# 7_RK3399_MIPI-CSI_I2C.net
KiCad netlist of a schematic drawn in Altium Designer
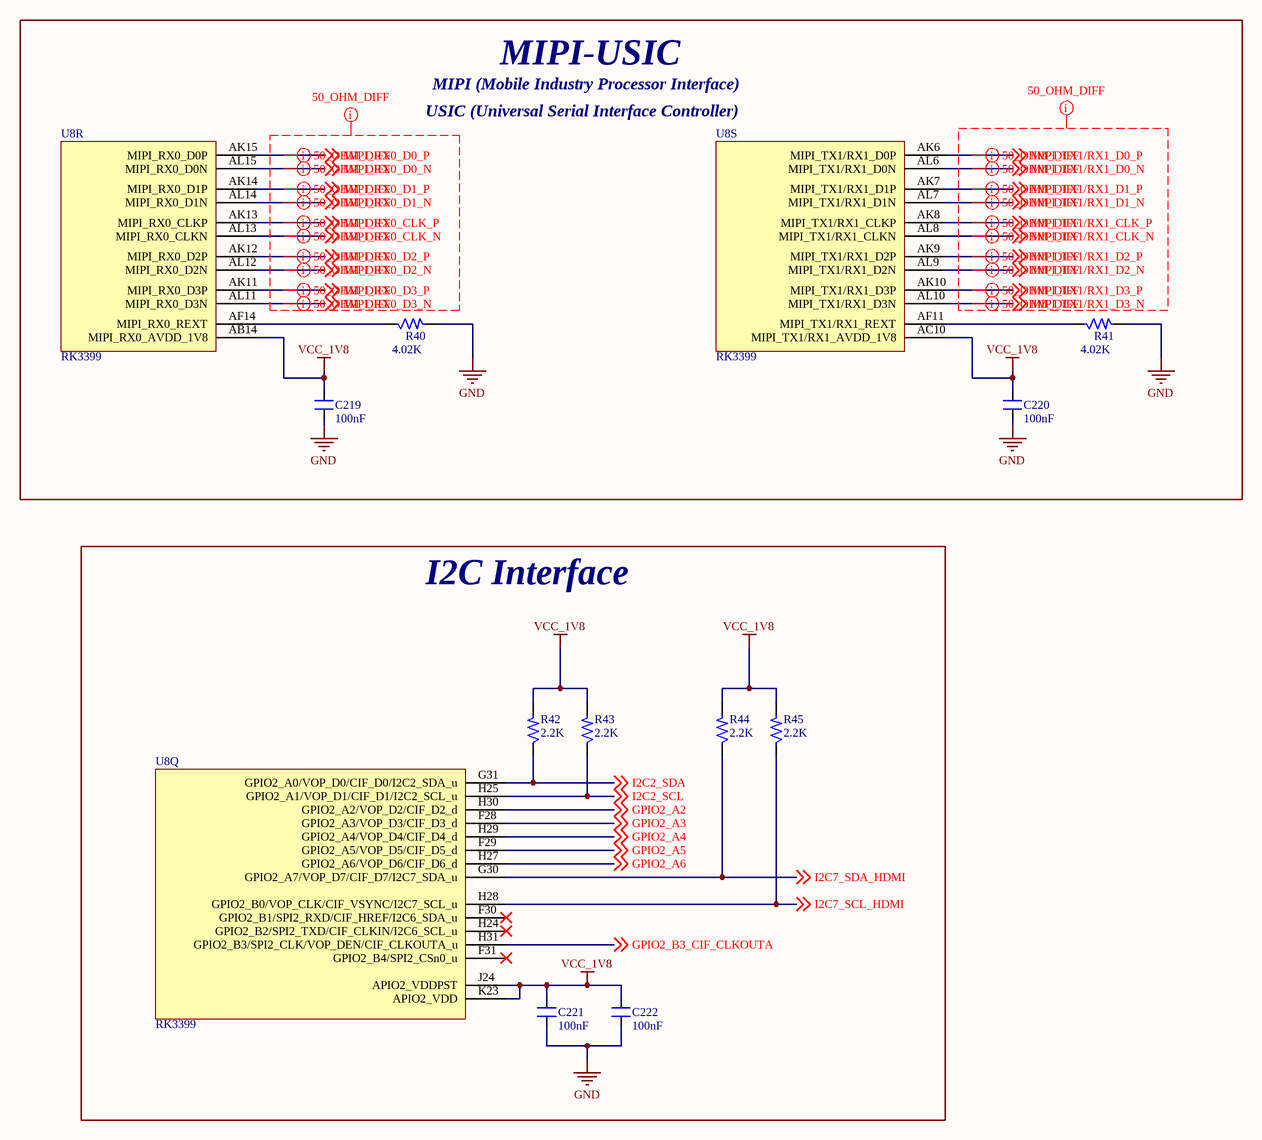
[diagram p0: [7] RK3399_MIPI-CSI_I2C.SchDoc]

(export (version "E")
  (design (tool "Eeschema 10.0.6"))
  (components
    (comp (ref "C219")
      (value "100nF")
      (footprint "CAP_0201")
      (description "0.1µF ±10% 25V Ceramic Capacitor X5R 0201 (0603 Metric)")
      (fields
        (field (name "MANUFACTURER") "TDK Corporation")
        (field (name "MANUFACTURER PART NUMBER") "C0603X5R1E104K030BB")
      )
      (libsource (lib "EsteemPCB_SOM_Course_intlib") (part "CAP_100nF-25V-10%-0201"))
    )
    (comp (ref "C220")
      (value "100nF")
      (footprint "CAP_0201")
      (description "0.1µF ±10% 25V Ceramic Capacitor X5R 0201 (0603 Metric)")
      (fields
        (field (name "MANUFACTURER") "TDK Corporation")
        (field (name "MANUFACTURER PART NUMBER") "C0603X5R1E104K030BB")
      )
      (libsource (lib "EsteemPCB_SOM_Course_intlib") (part "CAP_100nF-25V-10%-0201"))
    )
    (comp (ref "C221")
      (value "100nF")
      (footprint "CAP_0201")
      (description "0.1µF ±10% 25V Ceramic Capacitor X5R 0201 (0603 Metric)")
      (fields
        (field (name "MANUFACTURER") "TDK Corporation")
        (field (name "MANUFACTURER PART NUMBER") "C0603X5R1E104K030BB")
      )
      (libsource (lib "EsteemPCB_SOM_Course_intlib") (part "CAP_100nF-25V-10%-0201"))
    )
    (comp (ref "C222")
      (value "100nF")
      (footprint "CAP_0201")
      (description "0.1µF ±10% 25V Ceramic Capacitor X5R 0201 (0603 Metric)")
      (fields
        (field (name "MANUFACTURER") "TDK Corporation")
        (field (name "MANUFACTURER PART NUMBER") "C0603X5R1E104K030BB")
      )
      (libsource (lib "EsteemPCB_SOM_Course_intlib") (part "CAP_100nF-25V-10%-0201"))
    )
    (comp (ref "R40")
      (value "4.02K")
      (footprint "RES_0201")
      (description "4.02 kOhms ±1% 0.05W, 1/20W Chip Resistor 0201 (0603 Metric) Thick Film")
      (fields
        (field (name "MANUFACTURER") "Yageo")
        (field (name "MANUFACTURER PART NUMBER") "RC0201FR-074K02L")
      )
      (libsource (lib "EsteemPCB_SOM_Course_intlib") (part "RES_4.02K-0.05W-1%-0201"))
    )
    (comp (ref "R41")
      (value "4.02K")
      (footprint "RES_0201")
      (description "4.02 kOhms ±1% 0.05W, 1/20W Chip Resistor 0201 (0603 Metric) Thick Film")
      (fields
        (field (name "MANUFACTURER") "Yageo")
        (field (name "MANUFACTURER PART NUMBER") "RC0201FR-074K02L")
      )
      (libsource (lib "EsteemPCB_SOM_Course_intlib") (part "RES_4.02K-0.05W-1%-0201"))
    )
    (comp (ref "R42")
      (value "2.2K")
      (footprint "RES_0201")
      (description "2.2 kOhms ±1% 0.05W, 1/20W Chip Resistor 0201 (0603 Metric) Thick Film")
      (fields
        (field (name "MANUFACTURER") "Stackpole Electronics Inc")
        (field (name "MANUFACTURER PART NUMBER") "RMCF0201FT2K20")
      )
      (libsource (lib "EsteemPCB_SOM_Course_intlib") (part "RES_2.2K-0.05W-1%-0201"))
    )
    (comp (ref "R43")
      (value "2.2K")
      (footprint "RES_0201")
      (description "2.2 kOhms ±1% 0.05W, 1/20W Chip Resistor 0201 (0603 Metric) Thick Film")
      (fields
        (field (name "MANUFACTURER") "Stackpole Electronics Inc")
        (field (name "MANUFACTURER PART NUMBER") "RMCF0201FT2K20")
      )
      (libsource (lib "EsteemPCB_SOM_Course_intlib") (part "RES_2.2K-0.05W-1%-0201"))
    )
    (comp (ref "R44")
      (value "2.2K")
      (footprint "RES_0201")
      (description "2.2 kOhms ±1% 0.05W, 1/20W Chip Resistor 0201 (0603 Metric) Thick Film")
      (fields
        (field (name "MANUFACTURER") "Stackpole Electronics Inc")
        (field (name "MANUFACTURER PART NUMBER") "RMCF0201FT2K20")
      )
      (libsource (lib "EsteemPCB_SOM_Course_intlib") (part "RES_2.2K-0.05W-1%-0201"))
    )
    (comp (ref "R45")
      (value "2.2K")
      (footprint "RES_0201")
      (description "2.2 kOhms ±1% 0.05W, 1/20W Chip Resistor 0201 (0603 Metric) Thick Film")
      (fields
        (field (name "MANUFACTURER") "Stackpole Electronics Inc")
        (field (name "MANUFACTURER PART NUMBER") "RMCF0201FT2K20")
      )
      (libsource (lib "EsteemPCB_SOM_Course_intlib") (part "RES_2.2K-0.05W-1%-0201"))
    )
    (comp (ref "U8")
      (value "RK3399")
      (footprint "FBGA828_23_826X826")
      (description "RK3399 is a low power, high performance processor for computing, personal mobile.")
      (fields (field (name "MANUFACTURER") "Rockchip"))
      (libsource (lib "EsteemPCB_SOM_Course_intlib") (part "IC_RK3399-FCBGA828"))
    )
  )
  (nets
    (net (code "1") (name "GND") (class "Default")
      (node (ref "C219") (pin "1") (pinfunction "1_1") (pintype "passive"))
      (node (ref "C220") (pin "1") (pinfunction "1_1") (pintype "passive"))
      (node (ref "C221") (pin "1") (pinfunction "1_1") (pintype "passive"))
      (node (ref "C222") (pin "1") (pinfunction "1_1") (pintype "passive"))
      (node (ref "R40") (pin "2") (pinfunction "2_2") (pintype "passive"))
      (node (ref "R41") (pin "2") (pinfunction "2_2") (pintype "passive"))
    )
    (net (code "2") (name "GPIO2_A2") (class "Default")
      (node (ref "U8") (pin "H30") (pinfunction "GPIO2_A2/VOP_D2/CIF_D2_d_H30") (pintype "passive"))
    )
    (net (code "3") (name "GPIO2_A3") (class "Default")
      (node (ref "U8") (pin "F28") (pinfunction "GPIO2_A3/VOP_D3/CIF_D3_d_F28") (pintype "passive"))
    )
    (net (code "4") (name "GPIO2_A4") (class "Default")
      (node (ref "U8") (pin "H29") (pinfunction "GPIO2_A4/VOP_D4/CIF_D4_d_H29") (pintype "passive"))
    )
    (net (code "5") (name "GPIO2_A5") (class "Default")
      (node (ref "U8") (pin "F29") (pinfunction "GPIO2_A5/VOP_D5/CIF_D5_d_F29") (pintype "passive"))
    )
    (net (code "6") (name "GPIO2_A6") (class "Default")
      (node (ref "U8") (pin "H27") (pinfunction "GPIO2_A6/VOP_D6/CIF_D6_d_H27") (pintype "passive"))
    )
    (net (code "7") (name "GPIO2_B3_CIF_CLKOUTA") (class "Default")
      (node (ref "U8") (pin "H31") (pinfunction "GPIO2_B3/SPI2_CLK/VOP_DEN/CIF_CLKOUTA_u_H31") (pintype "passive"))
    )
    (net (code "8") (name "I2C2_SCL") (class "Default")
      (node (ref "R43") (pin "1") (pinfunction "1_1") (pintype "passive"))
      (node (ref "U8") (pin "H25") (pinfunction "GPIO2_A1/VOP_D1/CIF_D1/I2C2_SCL_u_H25") (pintype "passive"))
    )
    (net (code "9") (name "I2C2_SDA") (class "Default")
      (node (ref "R42") (pin "1") (pinfunction "1_1") (pintype "passive"))
      (node (ref "U8") (pin "G31") (pinfunction "GPIO2_A0/VOP_D0/CIF_D0/I2C2_SDA_u_G31") (pintype "passive"))
    )
    (net (code "10") (name "I2C7_SCL_HDMI") (class "Default")
      (node (ref "R45") (pin "1") (pinfunction "1_1") (pintype "passive"))
      (node (ref "U8") (pin "H28") (pinfunction "GPIO2_B0/VOP_CLK/CIF_VSYNC/I2C7_SCL_u_H28") (pintype "passive"))
    )
    (net (code "11") (name "I2C7_SDA_HDMI") (class "Default")
      (node (ref "R44") (pin "1") (pinfunction "1_1") (pintype "passive"))
      (node (ref "U8") (pin "G30") (pinfunction "GPIO2_A7/VOP_D7/CIF_D7/I2C7_SDA_u_G30") (pintype "passive"))
    )
    (net (code "12") (name "MIPI_RX0_CLK_N") (class "Default")
      (node (ref "U8") (pin "AL13") (pinfunction "MIPI_RX0_CLKN_AL13") (pintype "passive"))
    )
    (net (code "13") (name "MIPI_RX0_CLK_P") (class "Default")
      (node (ref "U8") (pin "AK13") (pinfunction "MIPI_RX0_CLKP_AK13") (pintype "passive"))
    )
    (net (code "14") (name "MIPI_RX0_D0_N") (class "Default")
      (node (ref "U8") (pin "AL15") (pinfunction "MIPI_RX0_D0N_AL15") (pintype "passive"))
    )
    (net (code "15") (name "MIPI_RX0_D0_P") (class "Default")
      (node (ref "U8") (pin "AK15") (pinfunction "MIPI_RX0_D0P_AK15") (pintype "passive"))
    )
    (net (code "16") (name "MIPI_RX0_D1_N") (class "Default")
      (node (ref "U8") (pin "AL14") (pinfunction "MIPI_RX0_D1N_AL14") (pintype "passive"))
    )
    (net (code "17") (name "MIPI_RX0_D1_P") (class "Default")
      (node (ref "U8") (pin "AK14") (pinfunction "MIPI_RX0_D1P_AK14") (pintype "passive"))
    )
    (net (code "18") (name "MIPI_RX0_D2_N") (class "Default")
      (node (ref "U8") (pin "AL12") (pinfunction "MIPI_RX0_D2N_AL12") (pintype "passive"))
    )
    (net (code "19") (name "MIPI_RX0_D2_P") (class "Default")
      (node (ref "U8") (pin "AK12") (pinfunction "MIPI_RX0_D2P_AK12") (pintype "passive"))
    )
    (net (code "20") (name "MIPI_RX0_D3_N") (class "Default")
      (node (ref "U8") (pin "AL11") (pinfunction "MIPI_RX0_D3N_AL11") (pintype "passive"))
    )
    (net (code "21") (name "MIPI_RX0_D3_P") (class "Default")
      (node (ref "U8") (pin "AK11") (pinfunction "MIPI_RX0_D3P_AK11") (pintype "passive"))
    )
    (net (code "22") (name "MIPI_TX1{slash}RX1_CLK_N") (class "Default")
      (node (ref "U8") (pin "AL8") (pinfunction "MIPI_TX1/RX1_CLKN_AL8") (pintype "passive"))
    )
    (net (code "23") (name "MIPI_TX1{slash}RX1_CLK_P") (class "Default")
      (node (ref "U8") (pin "AK8") (pinfunction "MIPI_TX1/RX1_CLKP_AK8") (pintype "passive"))
    )
    (net (code "24") (name "MIPI_TX1{slash}RX1_D0_N") (class "Default")
      (node (ref "U8") (pin "AL6") (pinfunction "MIPI_TX1/RX1_D0N_AL6") (pintype "passive"))
    )
    (net (code "25") (name "MIPI_TX1{slash}RX1_D0_P") (class "Default")
      (node (ref "U8") (pin "AK6") (pinfunction "MIPI_TX1/RX1_D0P_AK6") (pintype "passive"))
    )
    (net (code "26") (name "MIPI_TX1{slash}RX1_D1_N") (class "Default")
      (node (ref "U8") (pin "AL7") (pinfunction "MIPI_TX1/RX1_D1N_AL7") (pintype "passive"))
    )
    (net (code "27") (name "MIPI_TX1{slash}RX1_D1_P") (class "Default")
      (node (ref "U8") (pin "AK7") (pinfunction "MIPI_TX1/RX1_D1P_AK7") (pintype "passive"))
    )
    (net (code "28") (name "MIPI_TX1{slash}RX1_D2_N") (class "Default")
      (node (ref "U8") (pin "AL9") (pinfunction "MIPI_TX1/RX1_D2N_AL9") (pintype "passive"))
    )
    (net (code "29") (name "MIPI_TX1{slash}RX1_D2_P") (class "Default")
      (node (ref "U8") (pin "AK9") (pinfunction "MIPI_TX1/RX1_D2P_AK9") (pintype "passive"))
    )
    (net (code "30") (name "MIPI_TX1{slash}RX1_D3_N") (class "Default")
      (node (ref "U8") (pin "AL10") (pinfunction "MIPI_TX1/RX1_D3N_AL10") (pintype "passive"))
    )
    (net (code "31") (name "MIPI_TX1{slash}RX1_D3_P") (class "Default")
      (node (ref "U8") (pin "AK10") (pinfunction "MIPI_TX1/RX1_D3P_AK10") (pintype "passive"))
    )
    (net (code "32") (name "Net-(U8R-MIPI_RX0_REXT)") (class "Default")
      (node (ref "R40") (pin "1") (pinfunction "1_1") (pintype "passive"))
      (node (ref "U8") (pin "AF14") (pinfunction "MIPI_RX0_REXT_AF14") (pintype "passive"))
    )
    (net (code "33") (name "Net-(U8S-MIPI_TX1{slash}RX1_REXT)") (class "Default")
      (node (ref "R41") (pin "1") (pinfunction "1_1") (pintype "passive"))
      (node (ref "U8") (pin "AF11") (pinfunction "MIPI_TX1/RX1_REXT_AF11") (pintype "passive"))
    )
    (net (code "34") (name "VCC_1V8") (class "Default")
      (node (ref "C219") (pin "2") (pinfunction "2_2") (pintype "passive"))
      (node (ref "C220") (pin "2") (pinfunction "2_2") (pintype "passive"))
      (node (ref "C221") (pin "2") (pinfunction "2_2") (pintype "passive"))
      (node (ref "C222") (pin "2") (pinfunction "2_2") (pintype "passive"))
      (node (ref "R42") (pin "2") (pinfunction "2_2") (pintype "passive"))
      (node (ref "R43") (pin "2") (pinfunction "2_2") (pintype "passive"))
      (node (ref "R44") (pin "2") (pinfunction "2_2") (pintype "passive"))
      (node (ref "R45") (pin "2") (pinfunction "2_2") (pintype "passive"))
      (node (ref "U8") (pin "AB14") (pinfunction "MIPI_RX0_AVDD_1V8_AB14") (pintype "passive"))
      (node (ref "U8") (pin "AC10") (pinfunction "MIPI_TX1/RX1_AVDD_1V8_AC10") (pintype "passive"))
      (node (ref "U8") (pin "J24") (pinfunction "APIO2_VDDPST_J24") (pintype "passive"))
      (node (ref "U8") (pin "K23") (pinfunction "APIO2_VDD_K23") (pintype "passive"))
    )
    (net (code "35") (name "unconnected-(U8Q-GPIO2_B1{slash}SPI2_RXD{slash}CIF_HREF{slash}I2C6_SDA_u-PadF30)") (class "Default")
      (node (ref "U8") (pin "F30") (pinfunction "GPIO2_B1/SPI2_RXD/CIF_HREF/I2C6_SDA_u_F30") (pintype "passive+no_connect"))
    )
    (net (code "36") (name "unconnected-(U8Q-GPIO2_B2{slash}SPI2_TXD{slash}CIF_CLKIN{slash}I2C6_SCL_u-PadH24)") (class "Default")
      (node (ref "U8") (pin "H24") (pinfunction "GPIO2_B2/SPI2_TXD/CIF_CLKIN/I2C6_SCL_u_H24") (pintype "passive+no_connect"))
    )
    (net (code "37") (name "unconnected-(U8Q-GPIO2_B4{slash}SPI2_CSn0_u-PadF31)") (class "Default")
      (node (ref "U8") (pin "F31") (pinfunction "GPIO2_B4/SPI2_CSn0_u_F31") (pintype "passive+no_connect"))
    )
  )
)
